# capSwitch.net
KiCad netlist of a schematic drawn in EAGLE
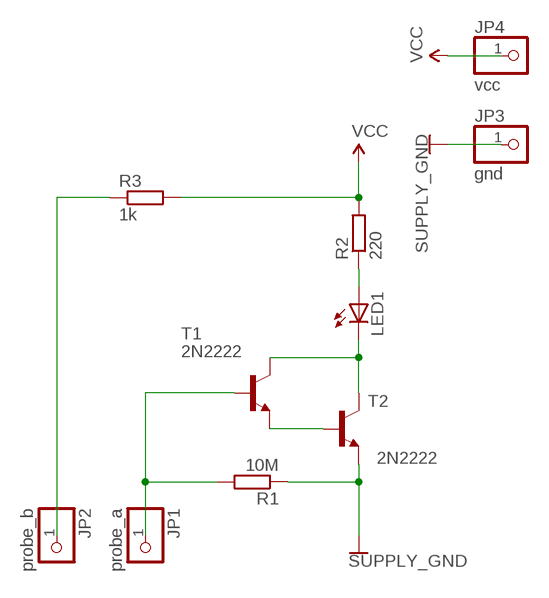
[diagram p0: schematic, sheet 1]

(export (version "E")
  (design (tool "Eeschema 10.0.6"))
  (components
    (comp (ref "JP1")
      (value "probe_a")
      (footprint "eagle-import:1X01_OVAL")
      (libsource (lib "eagle-import") (part "HEADER-1X1"))
    )
    (comp (ref "JP2")
      (value "probe_b")
      (footprint "eagle-import:1X01_OVAL")
      (libsource (lib "eagle-import") (part "HEADER-1X1"))
    )
    (comp (ref "JP3")
      (value "gnd")
      (footprint "eagle-import:1X01_OVAL")
      (libsource (lib "eagle-import") (part "HEADER-1X1"))
    )
    (comp (ref "JP4")
      (value "vcc")
      (footprint "eagle-import:1X01_OVAL")
      (libsource (lib "eagle-import") (part "HEADER-1X1"))
    )
    (comp (ref "LED1")
      (value "LED5MM")
      (footprint "eagle-import:LED5MM")
      (libsource (lib "eagle-import") (part "LED5MM"))
    )
    (comp (ref "R1")
      (value "10M")
      (footprint "eagle-import:RTH025W")
      (libsource (lib "eagle-import") (part "RESISTOR-PTH-0.4"))
    )
    (comp (ref "R2")
      (value "220")
      (footprint "eagle-import:RTH025W")
      (libsource (lib "eagle-import") (part "RESISTOR-PTH-0.4"))
    )
    (comp (ref "R3")
      (value "1k")
      (footprint "eagle-import:RTH025W")
      (libsource (lib "eagle-import") (part "RESISTOR-PTH-0.4"))
    )
    (comp (ref "T1")
      (value "2N2222")
      (footprint "eagle-import:TO92-EBC-OVAL")
      (libsource (lib "eagle-import") (part "2N2222"))
    )
    (comp (ref "T2")
      (value "2N2222")
      (footprint "eagle-import:TO92-EBC-OVAL")
      (libsource (lib "eagle-import") (part "2N2222"))
    )
  )
  (nets
    (net (code "1") (name "Net-(JP1-Pad1)") (class "Default")
      (node (ref "JP1") (pin "1") (pinfunction "1_1") (pintype "passive"))
      (node (ref "R1") (pin "2") (pinfunction "2_2") (pintype "passive"))
      (node (ref "T1") (pin "B") (pinfunction "B_B") (pintype "passive"))
    )
    (net (code "2") (name "Net-(JP2-Pad1)") (class "Default")
      (node (ref "JP2") (pin "1") (pinfunction "1_1") (pintype "passive"))
      (node (ref "R3") (pin "1") (pinfunction "1_1") (pintype "passive"))
    )
    (net (code "3") (name "Net-(LED1-C)") (class "Default")
      (node (ref "LED1") (pin "K") (pinfunction "C_K") (pintype "passive"))
      (node (ref "T1") (pin "C") (pinfunction "C_C") (pintype "passive"))
      (node (ref "T2") (pin "C") (pinfunction "C_C") (pintype "passive"))
    )
    (net (code "4") (name "Net-(LED1-PadA)") (class "Default")
      (node (ref "LED1") (pin "A") (pinfunction "A_A") (pintype "passive"))
      (node (ref "R2") (pin "1") (pinfunction "1_1") (pintype "passive"))
    )
    (net (code "5") (name "Net-(T1-PadE)") (class "Default")
      (node (ref "T1") (pin "E") (pinfunction "E_E") (pintype "passive"))
      (node (ref "T2") (pin "B") (pinfunction "B_B") (pintype "passive"))
    )
    (net (code "6") (name "SUPPLY_GND") (class "Default")
      (node (ref "JP3") (pin "1") (pinfunction "1_1") (pintype "passive"))
      (node (ref "R1") (pin "1") (pinfunction "1_1") (pintype "passive"))
      (node (ref "T2") (pin "E") (pinfunction "E_E") (pintype "passive"))
    )
    (net (code "7") (name "VCC") (class "Default")
      (node (ref "JP4") (pin "1") (pinfunction "1_1") (pintype "passive"))
      (node (ref "R2") (pin "2") (pinfunction "2_2") (pintype "passive"))
      (node (ref "R3") (pin "2") (pinfunction "2_2") (pintype "passive"))
    )
  )
)
